# 3V3Secondary.net
KiCad netlist of a schematic drawn in Altium Designer
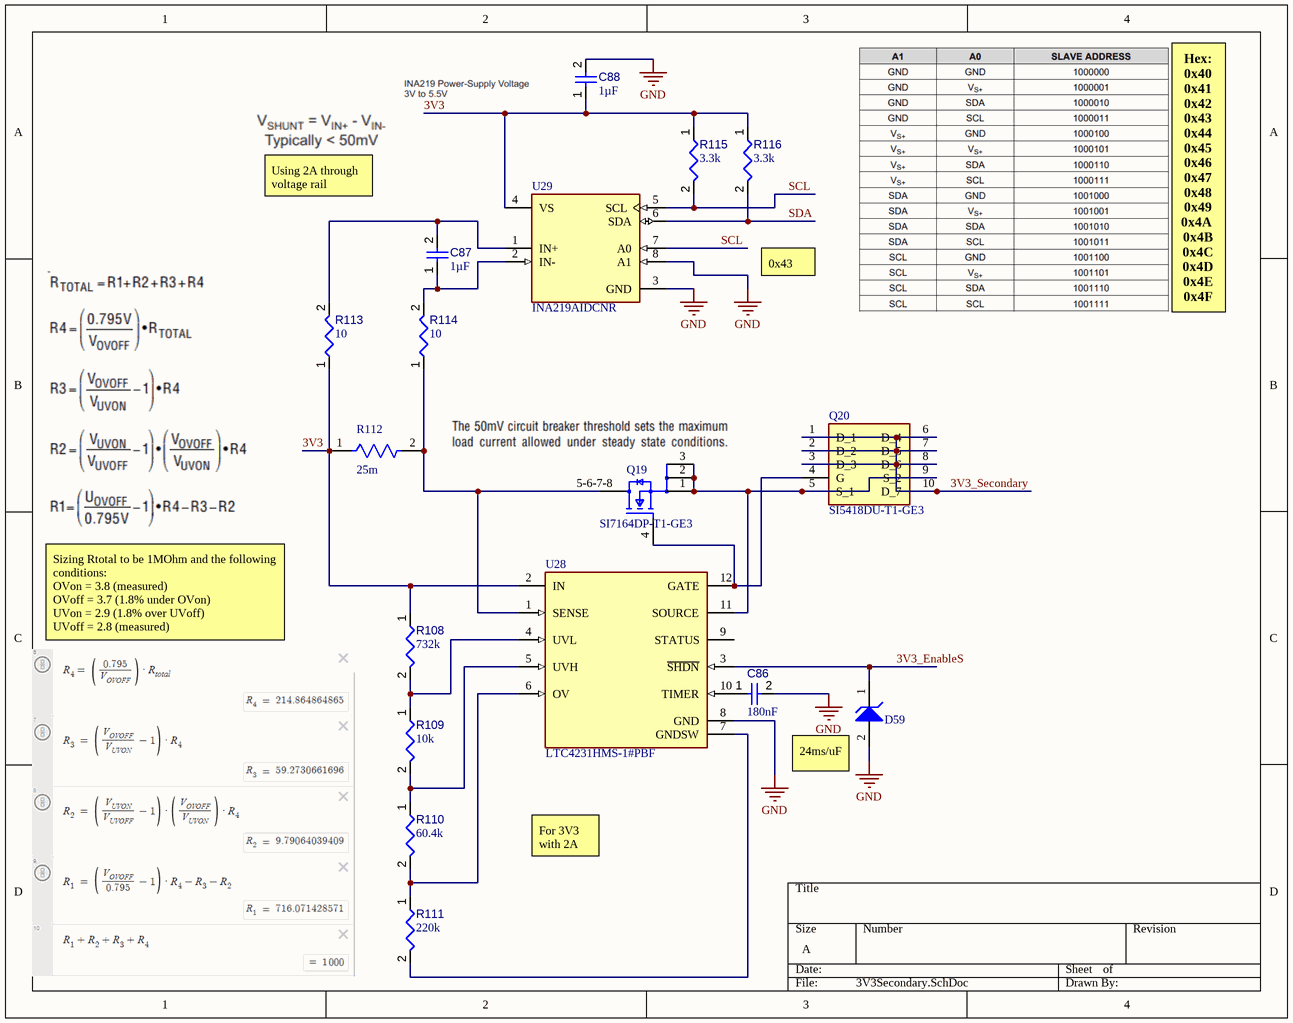
[diagram p0: 3V3Secondary.SchDoc]

(export (version "E")
  (design (tool "Eeschema 10.0.6"))
  (components
    (comp (ref "C86")
      (value "180nF")
      (footprint "FP-C0805C-DN-IPC_A")
      (fields (field (name "Comment") "C0805C184K5RACTU"))
      (libsource (lib "UGA SSRL Hardware Team") (part "CAP-NP-2"))
    )
    (comp (ref "C87")
      (value "1µF")
      (footprint "CAPC1608X90X40LL10T20")
      (description "Chip Capacitor, 1 uF, +/- 10%, 25 V, 0603 (1608 Metric)")
      (fields (field (name "TOLERANCE") "10%") (field (name "Comment") "Capacitor 1 uF +/- 10% 25 V 0603"))
      (libsource (lib "UGA SSRL Hardware Team") (part "CAP-NP-2"))
    )
    (comp (ref "C88")
      (value "1µF")
      (footprint "CAPC1608X90X35ML15T15")
      (description "Chip Capacitor, 1 uF, +/- 10%, 16 V, 0603 (1608 Metric)")
      (fields (field (name "TOLERANCE") "10%") (field (name "Comment") "Capacitor 1uF +/- 10% 16V 0603"))
      (libsource (lib "UGA SSRL Hardware Team") (part "CAP-NP-2"))
    )
    (comp (ref "D59")
      (value "MM3Z3V6T1G")
      (footprint "ONSC-SOD-323-2-477-02_V")
      (description "Zener Voltage Regulator, 300 mW, 2-Pin SOD-323, Pb-Free, Tape and Reel")
      (fields (field (name "MANUFACTURER") "On Semiconductor"))
      (libsource (lib "Altium Content Vault") (part "ONSC-K1A2-2"))
    )
    (comp (ref "Q19")
      (value "SI7164DP-T1-GE3")
      (footprint "Vishay_S17-0173-SINGLE_MFG")
      (libsource (lib "UGA SSRL Hardware Team") (part "SI7164DP-T1-GE3"))
    )
    (comp (ref "Q20")
      (value "SI5418DU-T1-GE3")
      (footprint "SI5418DU-T1-GE3-Footprint-1")
      (libsource (lib "UGA SSRL Hardware Team") (part "SI5418DU-T1-GE3-Symbol-1"))
    )
    (comp (ref "R108")
      (value "732k")
      (footprint "FP-CR0805-IPC_A")
      (fields
        (field (name "POWER") "125mW")
        (field (name "TOLERANCE") "1%")
        (field (name "Comment") "CR0805-FX-7323ELF")
      )
      (libsource (lib "UGA SSRL Hardware Team") (part "RES-2"))
    )
    (comp (ref "R109")
      (value "10k")
      (footprint "RESC1005X40X25ML05T05")
      (description "Chip Resistor, 10 KOhm, +/- 1%, 0.1 W, -55 to 155 degC, 0402 (1005 Metric)")
      (fields (field (name "TOLERANCE") "1%") (field (name "POWER") "100mW"))
      (libsource (lib "UGA SSRL Hardware Team") (part "RES-2"))
    )
    (comp (ref "R110")
      (value "60.4k")
      (footprint "RESC1005X40X25NL05T10")
      (fields
        (field (name "TOLERANCE") "1%")
        (field (name "POWER") "62.5mW")
        (field (name "Comment") "RC0402FR-0760K4L")
      )
      (libsource (lib "UGA SSRL Hardware Team") (part "RES-2"))
    )
    (comp (ref "R111")
      (value "220k")
      (footprint "FP-ESR01-IPC_C")
      (fields
        (field (name "POWER") "200mW")
        (field (name "TOLERANCE") "5%")
        (field (name "Comment") "ESR01MZPJ224")
      )
      (libsource (lib "UGA SSRL Hardware Team") (part "RES-2"))
    )
    (comp (ref "R112")
      (value "CSR1206FK25L0")
      (footprint "FP-CSR1206-IPC_C")
      (description "General Purpose Thick Film Chip Resistor, 1206, 25mΩ, 1%, 0.5W")
      (fields (field (name "RESISTANCE") "25m") (field (name "TOLERANCE") "1%"))
      (libsource (lib "Altium Content Vault") (part "1029c3af85768c4190bb7ad29bc67b5"))
    )
    (comp (ref "R113")
      (value "10")
      (footprint "RESC0402(1005)_L")
      (description "Chip Resistor, 10 Ohms, +/-1 %, 63 mW, -55 to 155 degC, 0402")
      (fields (field (name "TOLERANCE") "1%") (field (name "POWER") "63mW"))
      (libsource (lib "UGA SSRL Hardware Team") (part "RES-2"))
    )
    (comp (ref "R114")
      (value "10")
      (footprint "RESC0402(1005)_L")
      (description "Chip Resistor, 10 Ohms, +/-1 %, 63 mW, -55 to 155 degC, 0402")
      (fields (field (name "TOLERANCE") "1%") (field (name "POWER") "63mW"))
      (libsource (lib "UGA SSRL Hardware Team") (part "RES-2"))
    )
    (comp (ref "R115")
      (value "3.3k")
      (footprint "FP-CRCW1210-e3-IPC_C")
      (fields
        (field (name "TOLERANCE") "5%")
        (field (name "POWER") "500mW")
        (field (name "Comment") "CRCW12103K30JNEA")
      )
      (libsource (lib "UGA SSRL Hardware Team") (part "RES-2"))
    )
    (comp (ref "R116")
      (value "3.3k")
      (footprint "FP-CRCW1210-e3-IPC_C")
      (fields
        (field (name "TOLERANCE") "5%")
        (field (name "POWER") "500mW")
        (field (name "Comment") "CRCW12103K30JNEA")
      )
      (libsource (lib "UGA SSRL Hardware Team") (part "RES-2"))
    )
    (comp (ref "U28")
      (value "LTC4231HMS-1#PBF")
      (footprint "FP-MS-12-05-08-1668-MFG")
      (description "IC HOT SWAP CTRLR GP 12MSOP")
      (libsource (lib "Altium Content Vault") (part "22a006f8750c3b6cd4295fbd2c2f62c"))
    )
    (comp (ref "U29")
      (value "INA219AIDCNR")
      (footprint "FP-DCN0008A-IPC_A")
      (description "Power Supply Support Circuit, Fixed, 2 Channel, 2V, PDSO8")
      (libsource (lib "UGA SSRL Hardware Team") (part "e16934b8ef90d0e345b266f0ae9cd81"))
    )
  )
  (nets
    (net (code "1") (name "/3V3") (class "Default")
      (node (ref "C88") (pin "1") (pinfunction "1_1") (pintype "passive"))
      (node (ref "R108") (pin "1") (pinfunction "1_1") (pintype "passive"))
      (node (ref "R112") (pin "1") (pinfunction "1_1") (pintype "passive"))
      (node (ref "R113") (pin "1") (pinfunction "1_1") (pintype "passive"))
      (node (ref "R115") (pin "1") (pinfunction "1_1") (pintype "passive"))
      (node (ref "R116") (pin "1") (pinfunction "1_1") (pintype "passive"))
      (node (ref "U28") (pin "2") (pinfunction "IN_2") (pintype "power_in"))
      (node (ref "U29") (pin "4") (pinfunction "VS_4") (pintype "power_in"))
    )
    (net (code "2") (name "/3V3_EnableS") (class "Default")
      (node (ref "D59") (pin "1") (pinfunction "K_1") (pintype "passive"))
      (node (ref "U28") (pin "3") (pinfunction "~{SHDN}_3") (pintype "input"))
    )
    (net (code "3") (name "/3V3_Secondary") (class "Default")
      (node (ref "Q20") (pin "1") (pinfunction "D_1_1") (pintype "passive"))
      (node (ref "Q20") (pin "10") (pinfunction "D_7_10") (pintype "passive"))
      (node (ref "Q20") (pin "2") (pinfunction "D_2_2") (pintype "passive"))
      (node (ref "Q20") (pin "3") (pinfunction "D_3_3") (pintype "passive"))
      (node (ref "Q20") (pin "6") (pinfunction "D_4_6") (pintype "passive"))
      (node (ref "Q20") (pin "7") (pinfunction "D_5_7") (pintype "passive"))
      (node (ref "Q20") (pin "8") (pinfunction "D_6_8") (pintype "passive"))
    )
    (net (code "4") (name "/SCL") (class "Default")
      (node (ref "R115") (pin "2") (pinfunction "2_2") (pintype "passive"))
      (node (ref "U29") (pin "5") (pinfunction "SCL_5") (pintype "input"))
      (node (ref "U29") (pin "7") (pinfunction "A0_7") (pintype "input"))
    )
    (net (code "5") (name "/SDA") (class "Default")
      (node (ref "R116") (pin "2") (pinfunction "2_2") (pintype "passive"))
      (node (ref "U29") (pin "6") (pinfunction "SDA_6") (pintype "bidirectional"))
    )
    (net (code "6") (name "GND") (class "Default")
      (node (ref "C86") (pin "2") (pinfunction "2_2") (pintype "passive"))
      (node (ref "C88") (pin "2") (pinfunction "2_2") (pintype "passive"))
      (node (ref "D59") (pin "2") (pinfunction "A_2") (pintype "passive"))
      (node (ref "U28") (pin "8") (pinfunction "GND_8") (pintype "power_in"))
      (node (ref "U29") (pin "3") (pinfunction "GND_3") (pintype "power_in"))
      (node (ref "U29") (pin "8") (pinfunction "A1_8") (pintype "input"))
    )
    (net (code "7") (name "Net-(Q19-D)") (class "Default")
      (node (ref "Q19") (pin "5-6-7-8") (pinfunction "D_5-6-7-8") (pintype "passive"))
      (node (ref "R112") (pin "2") (pinfunction "2_2") (pintype "passive"))
      (node (ref "R114") (pin "1") (pinfunction "1_1") (pintype "passive"))
      (node (ref "U28") (pin "1") (pinfunction "SENSE_1") (pintype "input"))
    )
    (net (code "8") (name "Net-(Q19-G)") (class "Default")
      (node (ref "Q19") (pin "4") (pinfunction "G_4") (pintype "passive"))
      (node (ref "Q20") (pin "4") (pinfunction "G_4") (pintype "passive"))
      (node (ref "U28") (pin "12") (pinfunction "GATE_12") (pintype "passive"))
    )
    (net (code "9") (name "Net-(Q20-S_1)") (class "Default")
      (node (ref "Q19") (pin "1") (pinfunction "S_1") (pintype "passive"))
      (node (ref "Q19") (pin "2") (pinfunction "S_2") (pintype "passive"))
      (node (ref "Q19") (pin "3") (pinfunction "S_3") (pintype "passive"))
      (node (ref "Q20") (pin "5") (pinfunction "S_1_5") (pintype "passive"))
      (node (ref "Q20") (pin "9") (pinfunction "S_2_9") (pintype "passive"))
      (node (ref "U28") (pin "11") (pinfunction "SOURCE_11") (pintype "passive"))
    )
    (net (code "10") (name "Net-(U28-GNDSW)") (class "Default")
      (node (ref "R111") (pin "2") (pinfunction "2_2") (pintype "passive"))
      (node (ref "U28") (pin "7") (pinfunction "GNDSW_7") (pintype "power_in"))
    )
    (net (code "11") (name "Net-(U28-OV)") (class "Default")
      (node (ref "R110") (pin "2") (pinfunction "2_2") (pintype "passive"))
      (node (ref "R111") (pin "1") (pinfunction "1_1") (pintype "passive"))
      (node (ref "U28") (pin "6") (pinfunction "OV_6") (pintype "input"))
    )
    (net (code "12") (name "Net-(U28-TIMER)") (class "Default")
      (node (ref "C86") (pin "1") (pinfunction "1_1") (pintype "passive"))
      (node (ref "U28") (pin "10") (pinfunction "TIMER_10") (pintype "input"))
    )
    (net (code "13") (name "Net-(U28-UVH)") (class "Default")
      (node (ref "R109") (pin "2") (pinfunction "2_2") (pintype "passive"))
      (node (ref "R110") (pin "1") (pinfunction "1_1") (pintype "passive"))
      (node (ref "U28") (pin "5") (pinfunction "UVH_5") (pintype "input"))
    )
    (net (code "14") (name "Net-(U28-UVL)") (class "Default")
      (node (ref "R108") (pin "2") (pinfunction "2_2") (pintype "passive"))
      (node (ref "R109") (pin "1") (pinfunction "1_1") (pintype "passive"))
      (node (ref "U28") (pin "4") (pinfunction "UVL_4") (pintype "input"))
    )
    (net (code "15") (name "Net-(U29-IN+)") (class "Default")
      (node (ref "C87") (pin "2") (pinfunction "2_2") (pintype "passive"))
      (node (ref "R113") (pin "2") (pinfunction "2_2") (pintype "passive"))
      (node (ref "U29") (pin "1") (pinfunction "IN+_1") (pintype "passive"))
    )
    (net (code "16") (name "Net-(U29-IN-)") (class "Default")
      (node (ref "C87") (pin "1") (pinfunction "1_1") (pintype "passive"))
      (node (ref "R114") (pin "2") (pinfunction "2_2") (pintype "passive"))
      (node (ref "U29") (pin "2") (pinfunction "IN-_2") (pintype "input"))
    )
    (net (code "17") (name "unconnected-(U28-STATUS-Pad9)") (class "Default")
      (node (ref "U28") (pin "9") (pinfunction "STATUS_9") (pintype "open_collector"))
    )
  )
)
